# 7SegClock.net
KiCad netlist of a schematic drawn in EAGLE
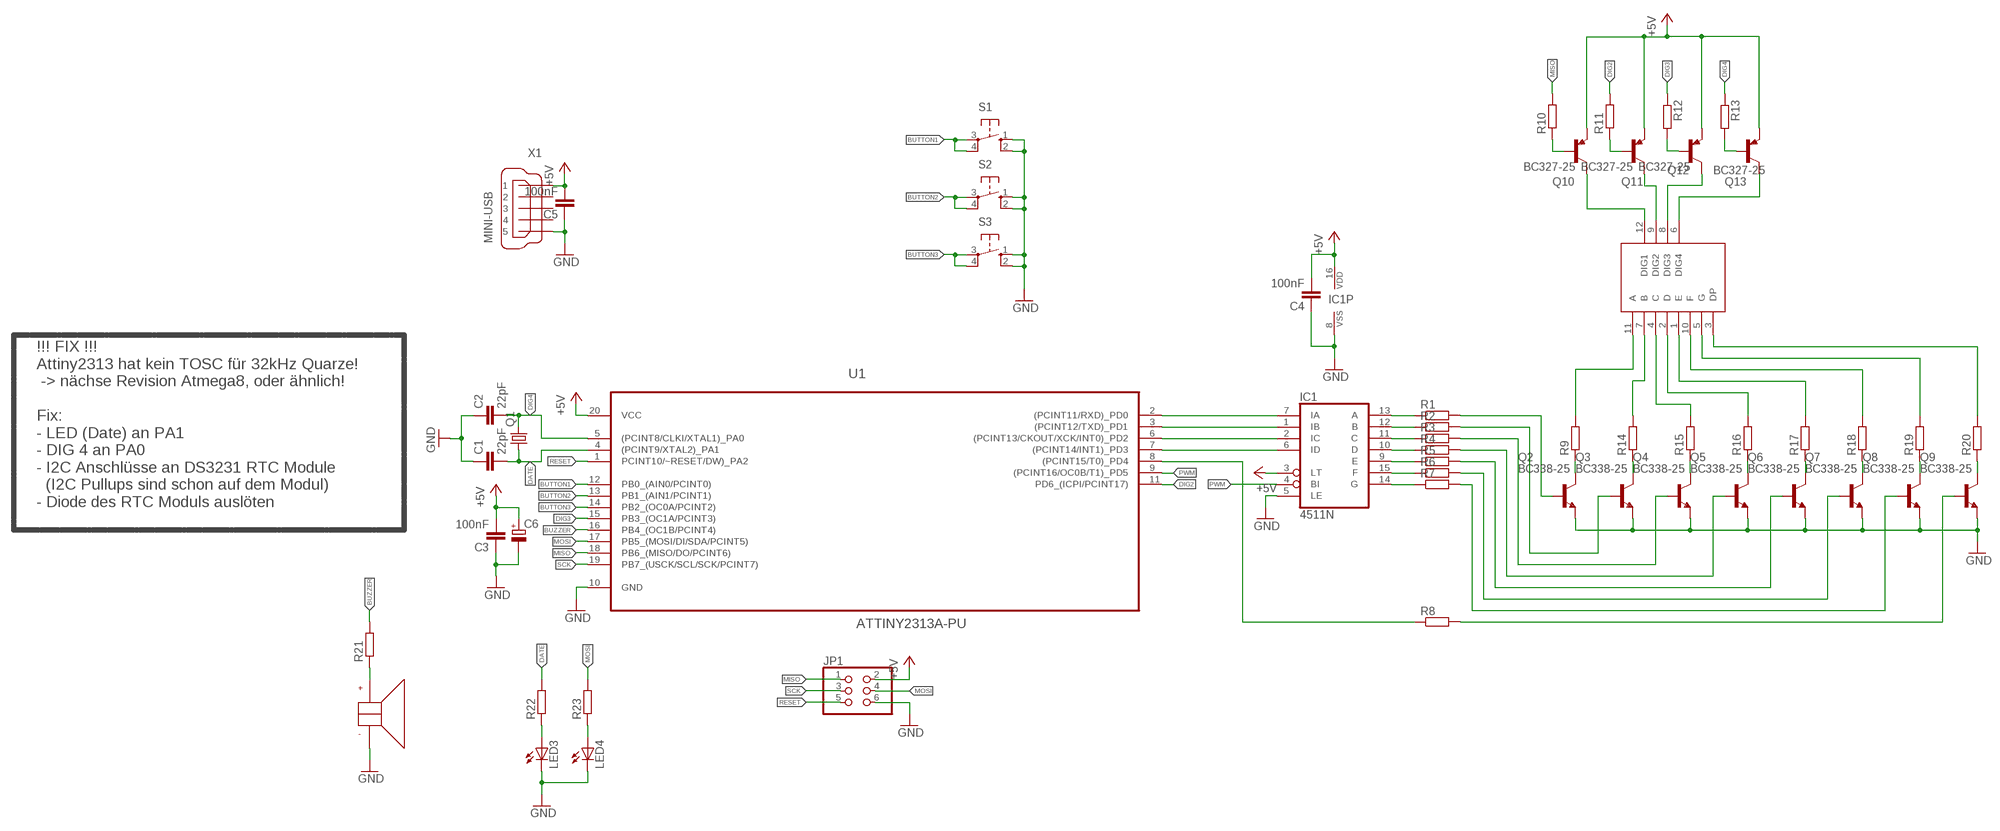
[diagram p0: schematic, sheet 1]

(export (version "E")
  (design (tool "Eeschema 10.0.6"))
  (components
    (comp (ref "C1")
      (value "22pF")
      (footprint "eagle-import:C025-025X050")
      (libsource (lib "eagle-import") (part "C-EU025-025X050"))
    )
    (comp (ref "C2")
      (value "22pF")
      (footprint "eagle-import:C025-025X050")
      (libsource (lib "eagle-import") (part "C-EU025-025X050"))
    )
    (comp (ref "C3")
      (value "100nF")
      (footprint "eagle-import:C025-025X050")
      (libsource (lib "eagle-import") (part "C-EU025-025X050"))
    )
    (comp (ref "C4")
      (value "100nF")
      (footprint "eagle-import:C025-025X050")
      (libsource (lib "eagle-import") (part "C-EU025-025X050"))
    )
    (comp (ref "C5")
      (value "100nF")
      (footprint "eagle-import:C025-025X050")
      (libsource (lib "eagle-import") (part "C-EU025-025X050"))
    )
    (comp (ref "C6")
      (value "CPOL-EUE2-5")
      (footprint "eagle-import:E2-5")
      (libsource (lib "eagle-import") (part "CPOL-EUE2-5"))
    )
    (comp (ref "IC1")
      (value "4511N")
      (footprint "eagle-import:DIL16")
      (libsource (lib "eagle-import") (part "4511N"))
    )
    (comp (ref "JP1")
      (value "PINHD-2X3")
      (footprint "eagle-import:2X03")
      (libsource (lib "eagle-import") (part "PINHD-2X3"))
    )
    (comp (ref "LED1")
      (value "7SEGCOMAN")
      (footprint "eagle-import:7SEGCOMAN")
      (libsource (lib "eagle-import") (part "7SEGCOMAN"))
    )
    (comp (ref "LED3")
      (value "LED3MM")
      (footprint "eagle-import:LED3MM")
      (libsource (lib "eagle-import") (part "LED3MM"))
    )
    (comp (ref "LED4")
      (value "LED3MM")
      (footprint "eagle-import:LED3MM")
      (libsource (lib "eagle-import") (part "LED3MM"))
    )
    (comp (ref "Q1")
      (value "CRYSTALTC38H")
      (footprint "eagle-import:TC38H")
      (libsource (lib "eagle-import") (part "CRYSTALTC38H"))
    )
    (comp (ref "Q2")
      (value "BC338-25")
      (footprint "eagle-import:TO92-EBC")
      (libsource (lib "eagle-import") (part "BC338-25"))
    )
    (comp (ref "Q3")
      (value "BC338-25")
      (footprint "eagle-import:TO92-EBC")
      (libsource (lib "eagle-import") (part "BC338-25"))
    )
    (comp (ref "Q4")
      (value "BC338-25")
      (footprint "eagle-import:TO92-EBC")
      (libsource (lib "eagle-import") (part "BC338-25"))
    )
    (comp (ref "Q5")
      (value "BC338-25")
      (footprint "eagle-import:TO92-EBC")
      (libsource (lib "eagle-import") (part "BC338-25"))
    )
    (comp (ref "Q6")
      (value "BC338-25")
      (footprint "eagle-import:TO92-EBC")
      (libsource (lib "eagle-import") (part "BC338-25"))
    )
    (comp (ref "Q7")
      (value "BC338-25")
      (footprint "eagle-import:TO92-EBC")
      (libsource (lib "eagle-import") (part "BC338-25"))
    )
    (comp (ref "Q8")
      (value "BC338-25")
      (footprint "eagle-import:TO92-EBC")
      (libsource (lib "eagle-import") (part "BC338-25"))
    )
    (comp (ref "Q9")
      (value "BC338-25")
      (footprint "eagle-import:TO92-EBC")
      (libsource (lib "eagle-import") (part "BC338-25"))
    )
    (comp (ref "Q10")
      (value "BC327-25")
      (footprint "eagle-import:TO92-EBC")
      (libsource (lib "eagle-import") (part "BC327-25"))
    )
    (comp (ref "Q11")
      (value "BC327-25")
      (footprint "eagle-import:TO92-EBC")
      (libsource (lib "eagle-import") (part "BC327-25"))
    )
    (comp (ref "Q12")
      (value "BC327-25")
      (footprint "eagle-import:TO92-EBC")
      (libsource (lib "eagle-import") (part "BC327-25"))
    )
    (comp (ref "Q13")
      (value "BC327-25")
      (footprint "eagle-import:TO92-EBC")
      (libsource (lib "eagle-import") (part "BC327-25"))
    )
    (comp (ref "R1")
      (value "R-EU_0207/7")
      (footprint "eagle-import:0207_7")
      (libsource (lib "eagle-import") (part "R-EU_0207/7"))
    )
    (comp (ref "R2")
      (value "R-EU_0207/7")
      (footprint "eagle-import:0207_7")
      (libsource (lib "eagle-import") (part "R-EU_0207/7"))
    )
    (comp (ref "R3")
      (value "R-EU_0207/7")
      (footprint "eagle-import:0207_7")
      (libsource (lib "eagle-import") (part "R-EU_0207/7"))
    )
    (comp (ref "R4")
      (value "R-EU_0207/7")
      (footprint "eagle-import:0207_7")
      (libsource (lib "eagle-import") (part "R-EU_0207/7"))
    )
    (comp (ref "R5")
      (value "R-EU_0207/7")
      (footprint "eagle-import:0207_7")
      (libsource (lib "eagle-import") (part "R-EU_0207/7"))
    )
    (comp (ref "R6")
      (value "R-EU_0207/7")
      (footprint "eagle-import:0207_7")
      (libsource (lib "eagle-import") (part "R-EU_0207/7"))
    )
    (comp (ref "R7")
      (value "R-EU_0207/7")
      (footprint "eagle-import:0207_7")
      (libsource (lib "eagle-import") (part "R-EU_0207/7"))
    )
    (comp (ref "R8")
      (value "R-EU_0207/7")
      (footprint "eagle-import:0207_7")
      (libsource (lib "eagle-import") (part "R-EU_0207/7"))
    )
    (comp (ref "R9")
      (value "R-EU_0207/7")
      (footprint "eagle-import:0207_7")
      (libsource (lib "eagle-import") (part "R-EU_0207/7"))
    )
    (comp (ref "R10")
      (value "R-EU_0207/7")
      (footprint "eagle-import:0207_7")
      (libsource (lib "eagle-import") (part "R-EU_0207/7"))
    )
    (comp (ref "R11")
      (value "R-EU_0207/7")
      (footprint "eagle-import:0207_7")
      (libsource (lib "eagle-import") (part "R-EU_0207/7"))
    )
    (comp (ref "R12")
      (value "R-EU_0207/7")
      (footprint "eagle-import:0207_7")
      (libsource (lib "eagle-import") (part "R-EU_0207/7"))
    )
    (comp (ref "R13")
      (value "R-EU_0207/7")
      (footprint "eagle-import:0207_7")
      (libsource (lib "eagle-import") (part "R-EU_0207/7"))
    )
    (comp (ref "R14")
      (value "R-EU_0207/7")
      (footprint "eagle-import:0207_7")
      (libsource (lib "eagle-import") (part "R-EU_0207/7"))
    )
    (comp (ref "R15")
      (value "R-EU_0207/7")
      (footprint "eagle-import:0207_7")
      (libsource (lib "eagle-import") (part "R-EU_0207/7"))
    )
    (comp (ref "R16")
      (value "R-EU_0207/7")
      (footprint "eagle-import:0207_7")
      (libsource (lib "eagle-import") (part "R-EU_0207/7"))
    )
    (comp (ref "R17")
      (value "R-EU_0207/7")
      (footprint "eagle-import:0207_7")
      (libsource (lib "eagle-import") (part "R-EU_0207/7"))
    )
    (comp (ref "R18")
      (value "R-EU_0207/7")
      (footprint "eagle-import:0207_7")
      (libsource (lib "eagle-import") (part "R-EU_0207/7"))
    )
    (comp (ref "R19")
      (value "R-EU_0207/7")
      (footprint "eagle-import:0207_7")
      (libsource (lib "eagle-import") (part "R-EU_0207/7"))
    )
    (comp (ref "R20")
      (value "R-EU_0207/7")
      (footprint "eagle-import:0207_7")
      (libsource (lib "eagle-import") (part "R-EU_0207/7"))
    )
    (comp (ref "R21")
      (value "R-EU_0207/7")
      (footprint "eagle-import:0207_7")
      (libsource (lib "eagle-import") (part "R-EU_0207/7"))
    )
    (comp (ref "R22")
      (value "R-EU_0207/7")
      (footprint "eagle-import:0207_7")
      (libsource (lib "eagle-import") (part "R-EU_0207/7"))
    )
    (comp (ref "R23")
      (value "R-EU_0207/7")
      (footprint "eagle-import:0207_7")
      (libsource (lib "eagle-import") (part "R-EU_0207/7"))
    )
    (comp (ref "S1")
      (value "10-XX")
      (footprint "eagle-import:B3F-10XX")
      (fields (field (name "MPN") "B3F-1000"))
      (libsource (lib "eagle-import") (part "10-XX"))
    )
    (comp (ref "S2")
      (value "10-XX")
      (footprint "eagle-import:B3F-10XX")
      (fields (field (name "MPN") "B3F-1000"))
      (libsource (lib "eagle-import") (part "10-XX"))
    )
    (comp (ref "S3")
      (value "10-XX")
      (footprint "eagle-import:B3F-10XX")
      (fields (field (name "MPN") "B3F-1000"))
      (libsource (lib "eagle-import") (part "10-XX"))
    )
    (comp (ref "U$1")
      (value "PIEZO_BUZZER_RM7,6")
      (footprint "eagle-import:PIEZO_BUZZER_RM7,6")
      (libsource (lib "eagle-import") (part "PIEZO_BUZZER_RM7,6"))
    )
    (comp (ref "U1")
      (value "ATTINY2313A-PU")
      (footprint "eagle-import:DIP254P762X533-20")
      (libsource (lib "eagle-import") (part "ATTINY2313A-PU"))
    )
    (comp (ref "X1")
      (value "MINI-USB")
      (footprint "eagle-import:32005-201")
      (libsource (lib "eagle-import") (part "MINI-USB-32005-201"))
    )
  )
  (nets
    (net (code "1") (name "+5V") (class "Default")
      (node (ref "C3") (pin "2") (pinfunction "2_2") (pintype "passive"))
      (node (ref "C4") (pin "2") (pinfunction "2_2") (pintype "passive"))
      (node (ref "C5") (pin "2") (pinfunction "2_2") (pintype "passive"))
      (node (ref "C6") (pin "+") (pinfunction "+_+") (pintype "passive"))
      (node (ref "IC1") (pin "16") (pinfunction "VDD_16") (pintype "power_in"))
      (node (ref "IC1") (pin "3") (pinfunction "LT_3") (pintype "input"))
      (node (ref "JP1") (pin "2") (pinfunction "2_2") (pintype "passive"))
      (node (ref "Q10") (pin "E") (pinfunction "E_E") (pintype "passive"))
      (node (ref "Q11") (pin "E") (pinfunction "E_E") (pintype "passive"))
      (node (ref "Q12") (pin "E") (pinfunction "E_E") (pintype "passive"))
      (node (ref "Q13") (pin "E") (pinfunction "E_E") (pintype "passive"))
      (node (ref "U1") (pin "20") (pinfunction "VCC_20") (pintype "power_in"))
      (node (ref "X1") (pin "1") (pinfunction "1_1") (pintype "passive"))
    )
    (net (code "2") (name "BUTTON1") (class "Default")
      (node (ref "S1") (pin "3") (pinfunction "P_3") (pintype "passive"))
      (node (ref "S1") (pin "4") (pinfunction "P1_4") (pintype "passive"))
      (node (ref "U1") (pin "12") (pinfunction "PB0_(AIN0/PCINT0)_12") (pintype "bidirectional"))
    )
    (net (code "3") (name "BUTTON2") (class "Default")
      (node (ref "S2") (pin "3") (pinfunction "P_3") (pintype "passive"))
      (node (ref "S2") (pin "4") (pinfunction "P1_4") (pintype "passive"))
      (node (ref "U1") (pin "13") (pinfunction "PB1_(AIN1/PCINT1)_13") (pintype "bidirectional"))
    )
    (net (code "4") (name "BUTTON3") (class "Default")
      (node (ref "S3") (pin "3") (pinfunction "P_3") (pintype "passive"))
      (node (ref "S3") (pin "4") (pinfunction "P1_4") (pintype "passive"))
      (node (ref "U1") (pin "14") (pinfunction "PB2_(OC0A/PCINT2)_14") (pintype "bidirectional"))
    )
    (net (code "5") (name "BUZZER") (class "Default")
      (node (ref "R21") (pin "2") (pinfunction "2_2") (pintype "passive"))
      (node (ref "U1") (pin "16") (pinfunction "PB4_(OC1B/PCINT4)_16") (pintype "bidirectional"))
    )
    (net (code "6") (name "DATE") (class "Default")
      (node (ref "C1") (pin "2") (pinfunction "2_2") (pintype "passive"))
      (node (ref "Q1") (pin "1") (pinfunction "1_1") (pintype "passive"))
      (node (ref "R22") (pin "2") (pinfunction "2_2") (pintype "passive"))
      (node (ref "U1") (pin "4") (pinfunction "(PCINT9/XTAL2)_PA1_4") (pintype "bidirectional"))
    )
    (net (code "7") (name "DIG2") (class "Default")
      (node (ref "R11") (pin "2") (pinfunction "2_2") (pintype "passive"))
      (node (ref "U1") (pin "11") (pinfunction "PD6_(ICPI/PCINT17)_11") (pintype "bidirectional"))
    )
    (net (code "8") (name "DIG3") (class "Default")
      (node (ref "R12") (pin "1") (pinfunction "1_1") (pintype "passive"))
      (node (ref "U1") (pin "15") (pinfunction "PB3_(OC1A/PCINT3)_15") (pintype "bidirectional"))
    )
    (net (code "9") (name "DIG4") (class "Default")
      (node (ref "C2") (pin "2") (pinfunction "2_2") (pintype "passive"))
      (node (ref "Q1") (pin "2") (pinfunction "2_2") (pintype "passive"))
      (node (ref "R13") (pin "1") (pinfunction "1_1") (pintype "passive"))
      (node (ref "U1") (pin "5") (pinfunction "(PCINT8/CLKI/XTAL1)_PA0_5") (pintype "bidirectional"))
    )
    (net (code "10") (name "GND") (class "Default")
      (node (ref "C1") (pin "1") (pinfunction "1_1") (pintype "passive"))
      (node (ref "C2") (pin "1") (pinfunction "1_1") (pintype "passive"))
      (node (ref "C3") (pin "1") (pinfunction "1_1") (pintype "passive"))
      (node (ref "C4") (pin "1") (pinfunction "1_1") (pintype "passive"))
      (node (ref "C5") (pin "1") (pinfunction "1_1") (pintype "passive"))
      (node (ref "C6") (pin "-") (pinfunction "-_-") (pintype "passive"))
      (node (ref "IC1") (pin "5") (pinfunction "LE_5") (pintype "input"))
      (node (ref "IC1") (pin "8") (pinfunction "VSS_8") (pintype "power_in"))
      (node (ref "JP1") (pin "6") (pinfunction "6_6") (pintype "passive"))
      (node (ref "LED3") (pin "K") (pinfunction "C_K") (pintype "passive"))
      (node (ref "LED4") (pin "K") (pinfunction "C_K") (pintype "passive"))
      (node (ref "Q2") (pin "E") (pinfunction "E_E") (pintype "passive"))
      (node (ref "Q3") (pin "E") (pinfunction "E_E") (pintype "passive"))
      (node (ref "Q4") (pin "E") (pinfunction "E_E") (pintype "passive"))
      (node (ref "Q5") (pin "E") (pinfunction "E_E") (pintype "passive"))
      (node (ref "Q6") (pin "E") (pinfunction "E_E") (pintype "passive"))
      (node (ref "Q7") (pin "E") (pinfunction "E_E") (pintype "passive"))
      (node (ref "Q8") (pin "E") (pinfunction "E_E") (pintype "passive"))
      (node (ref "Q9") (pin "E") (pinfunction "E_E") (pintype "passive"))
      (node (ref "S1") (pin "1") (pinfunction "S_1") (pintype "passive"))
      (node (ref "S1") (pin "2") (pinfunction "S1_2") (pintype "passive"))
      (node (ref "S2") (pin "1") (pinfunction "S_1") (pintype "passive"))
      (node (ref "S2") (pin "2") (pinfunction "S1_2") (pintype "passive"))
      (node (ref "S3") (pin "1") (pinfunction "S_1") (pintype "passive"))
      (node (ref "S3") (pin "2") (pinfunction "S1_2") (pintype "passive"))
      (node (ref "U$1") (pin "P$2") (pinfunction "P$2_P$2") (pintype "bidirectional"))
      (node (ref "U1") (pin "10") (pinfunction "GND_10") (pintype "passive"))
      (node (ref "X1") (pin "5") (pinfunction "5_5") (pintype "passive"))
    )
    (net (code "11") (name "MISO") (class "Default")
      (node (ref "JP1") (pin "1") (pinfunction "1_1") (pintype "passive"))
      (node (ref "R10") (pin "2") (pinfunction "2_2") (pintype "passive"))
      (node (ref "U1") (pin "18") (pinfunction "PB6_(MISO/DO/PCINT6)_18") (pintype "bidirectional"))
    )
    (net (code "12") (name "MOSI") (class "Default")
      (node (ref "JP1") (pin "4") (pinfunction "4_4") (pintype "passive"))
      (node (ref "R23") (pin "2") (pinfunction "2_2") (pintype "passive"))
      (node (ref "U1") (pin "17") (pinfunction "PB5_(MOSI/DI/SDA/PCINT5)_17") (pintype "bidirectional"))
    )
    (net (code "13") (name "Net-(IC1A-A)") (class "Default")
      (node (ref "IC1") (pin "13") (pinfunction "A_13") (pintype "output"))
      (node (ref "R1") (pin "1") (pinfunction "1_1") (pintype "passive"))
    )
    (net (code "14") (name "Net-(IC1A-B)") (class "Default")
      (node (ref "IC1") (pin "12") (pinfunction "B_12") (pintype "output"))
      (node (ref "R2") (pin "1") (pinfunction "1_1") (pintype "passive"))
    )
    (net (code "15") (name "Net-(IC1A-C)") (class "Default")
      (node (ref "IC1") (pin "11") (pinfunction "C_11") (pintype "output"))
      (node (ref "R3") (pin "1") (pinfunction "1_1") (pintype "passive"))
    )
    (net (code "16") (name "Net-(IC1A-D)") (class "Default")
      (node (ref "IC1") (pin "10") (pinfunction "D_10") (pintype "output"))
      (node (ref "R4") (pin "1") (pinfunction "1_1") (pintype "passive"))
    )
    (net (code "17") (name "Net-(IC1A-E)") (class "Default")
      (node (ref "IC1") (pin "9") (pinfunction "E_9") (pintype "output"))
      (node (ref "R5") (pin "1") (pinfunction "1_1") (pintype "passive"))
    )
    (net (code "18") (name "Net-(IC1A-F)") (class "Default")
      (node (ref "IC1") (pin "15") (pinfunction "F_15") (pintype "output"))
      (node (ref "R6") (pin "1") (pinfunction "1_1") (pintype "passive"))
    )
    (net (code "19") (name "Net-(IC1A-G)") (class "Default")
      (node (ref "IC1") (pin "14") (pinfunction "G_14") (pintype "output"))
      (node (ref "R7") (pin "1") (pinfunction "1_1") (pintype "passive"))
    )
    (net (code "20") (name "Net-(IC1A-IA)") (class "Default")
      (node (ref "IC1") (pin "7") (pinfunction "IA_7") (pintype "input"))
      (node (ref "U1") (pin "2") (pinfunction "(PCINT11/RXD)_PD0_2") (pintype "bidirectional"))
    )
    (net (code "21") (name "Net-(IC1A-IB)") (class "Default")
      (node (ref "IC1") (pin "1") (pinfunction "IB_1") (pintype "input"))
      (node (ref "U1") (pin "3") (pinfunction "(PCINT12/TXD)_PD1_3") (pintype "bidirectional"))
    )
    (net (code "22") (name "Net-(IC1A-IC)") (class "Default")
      (node (ref "IC1") (pin "2") (pinfunction "IC_2") (pintype "input"))
      (node (ref "U1") (pin "6") (pinfunction "(PCINT13/CKOUT/XCK/INT0)_PD2_6") (pintype "bidirectional"))
    )
    (net (code "23") (name "Net-(IC1A-ID)") (class "Default")
      (node (ref "IC1") (pin "6") (pinfunction "ID_6") (pintype "input"))
      (node (ref "U1") (pin "7") (pinfunction "(PCINT14/INT1)_PD3_7") (pintype "bidirectional"))
    )
    (net (code "24") (name "Net-(LED1-A)") (class "Default")
      (node (ref "LED1") (pin "11") (pinfunction "A_11") (pintype "bidirectional"))
      (node (ref "R9") (pin "2") (pinfunction "2_2") (pintype "passive"))
    )
    (net (code "25") (name "Net-(LED1-B)") (class "Default")
      (node (ref "LED1") (pin "7") (pinfunction "B_7") (pintype "bidirectional"))
      (node (ref "R14") (pin "2") (pinfunction "2_2") (pintype "passive"))
    )
    (net (code "26") (name "Net-(LED1-C)") (class "Default")
      (node (ref "LED1") (pin "4") (pinfunction "C_4") (pintype "bidirectional"))
      (node (ref "R15") (pin "2") (pinfunction "2_2") (pintype "passive"))
    )
    (net (code "27") (name "Net-(LED1-D)") (class "Default")
      (node (ref "LED1") (pin "2") (pinfunction "D_2") (pintype "bidirectional"))
      (node (ref "R16") (pin "2") (pinfunction "2_2") (pintype "passive"))
    )
    (net (code "28") (name "Net-(LED1-DIG1)") (class "Default")
      (node (ref "LED1") (pin "12") (pinfunction "DIG1_12") (pintype "bidirectional"))
      (node (ref "Q10") (pin "C") (pinfunction "C_C") (pintype "passive"))
    )
    (net (code "29") (name "Net-(LED1-DIG2)") (class "Default")
      (node (ref "LED1") (pin "9") (pinfunction "DIG2_9") (pintype "bidirectional"))
      (node (ref "Q11") (pin "C") (pinfunction "C_C") (pintype "passive"))
    )
    (net (code "30") (name "Net-(LED1-DIG3)") (class "Default")
      (node (ref "LED1") (pin "8") (pinfunction "DIG3_8") (pintype "bidirectional"))
      (node (ref "Q12") (pin "C") (pinfunction "C_C") (pintype "passive"))
    )
    (net (code "31") (name "Net-(LED1-DIG4)") (class "Default")
      (node (ref "LED1") (pin "6") (pinfunction "DIG4_6") (pintype "bidirectional"))
      (node (ref "Q13") (pin "C") (pinfunction "C_C") (pintype "passive"))
    )
    (net (code "32") (name "Net-(LED1-DP)") (class "Default")
      (node (ref "LED1") (pin "3") (pinfunction "DP_3") (pintype "bidirectional"))
      (node (ref "R20") (pin "2") (pinfunction "2_2") (pintype "passive"))
    )
    (net (code "33") (name "Net-(LED1-E)") (class "Default")
      (node (ref "LED1") (pin "1") (pinfunction "E_1") (pintype "bidirectional"))
      (node (ref "R17") (pin "2") (pinfunction "2_2") (pintype "passive"))
    )
    (net (code "34") (name "Net-(LED1-F)") (class "Default")
      (node (ref "LED1") (pin "10") (pinfunction "F_10") (pintype "bidirectional"))
      (node (ref "R18") (pin "2") (pinfunction "2_2") (pintype "passive"))
    )
    (net (code "35") (name "Net-(LED1-G)") (class "Default")
      (node (ref "LED1") (pin "5") (pinfunction "G_5") (pintype "bidirectional"))
      (node (ref "R19") (pin "2") (pinfunction "2_2") (pintype "passive"))
    )
    (net (code "36") (name "Net-(LED3-PadA)") (class "Default")
      (node (ref "LED3") (pin "A") (pinfunction "A_A") (pintype "passive"))
      (node (ref "R22") (pin "1") (pinfunction "1_1") (pintype "passive"))
    )
    (net (code "37") (name "Net-(LED4-PadA)") (class "Default")
      (node (ref "LED4") (pin "A") (pinfunction "A_A") (pintype "passive"))
      (node (ref "R23") (pin "1") (pinfunction "1_1") (pintype "passive"))
    )
    (net (code "38") (name "Net-(Q2-PadB)") (class "Default")
      (node (ref "Q2") (pin "B") (pinfunction "B_B") (pintype "passive"))
      (node (ref "R1") (pin "2") (pinfunction "2_2") (pintype "passive"))
    )
    (net (code "39") (name "Net-(Q2-PadC)") (class "Default")
      (node (ref "Q2") (pin "C") (pinfunction "C_C") (pintype "passive"))
      (node (ref "R9") (pin "1") (pinfunction "1_1") (pintype "passive"))
    )
    (net (code "40") (name "Net-(Q3-PadB)") (class "Default")
      (node (ref "Q3") (pin "B") (pinfunction "B_B") (pintype "passive"))
      (node (ref "R2") (pin "2") (pinfunction "2_2") (pintype "passive"))
    )
    (net (code "41") (name "Net-(Q3-PadC)") (class "Default")
      (node (ref "Q3") (pin "C") (pinfunction "C_C") (pintype "passive"))
      (node (ref "R14") (pin "1") (pinfunction "1_1") (pintype "passive"))
    )
    (net (code "42") (name "Net-(Q4-PadB)") (class "Default")
      (node (ref "Q4") (pin "B") (pinfunction "B_B") (pintype "passive"))
      (node (ref "R3") (pin "2") (pinfunction "2_2") (pintype "passive"))
    )
    (net (code "43") (name "Net-(Q4-PadC)") (class "Default")
      (node (ref "Q4") (pin "C") (pinfunction "C_C") (pintype "passive"))
      (node (ref "R15") (pin "1") (pinfunction "1_1") (pintype "passive"))
    )
    (net (code "44") (name "Net-(Q5-PadB)") (class "Default")
      (node (ref "Q5") (pin "B") (pinfunction "B_B") (pintype "passive"))
      (node (ref "R4") (pin "2") (pinfunction "2_2") (pintype "passive"))
    )
    (net (code "45") (name "Net-(Q5-PadC)") (class "Default")
      (node (ref "Q5") (pin "C") (pinfunction "C_C") (pintype "passive"))
      (node (ref "R16") (pin "1") (pinfunction "1_1") (pintype "passive"))
    )
    (net (code "46") (name "Net-(Q6-PadB)") (class "Default")
      (node (ref "Q6") (pin "B") (pinfunction "B_B") (pintype "passive"))
      (node (ref "R5") (pin "2") (pinfunction "2_2") (pintype "passive"))
    )
    (net (code "47") (name "Net-(Q6-PadC)") (class "Default")
      (node (ref "Q6") (pin "C") (pinfunction "C_C") (pintype "passive"))
      (node (ref "R17") (pin "1") (pinfunction "1_1") (pintype "passive"))
    )
    (net (code "48") (name "Net-(Q7-PadB)") (class "Default")
      (node (ref "Q7") (pin "B") (pinfunction "B_B") (pintype "passive"))
      (node (ref "R6") (pin "2") (pinfunction "2_2") (pintype "passive"))
    )
    (net (code "49") (name "Net-(Q7-PadC)") (class "Default")
      (node (ref "Q7") (pin "C") (pinfunction "C_C") (pintype "passive"))
      (node (ref "R18") (pin "1") (pinfunction "1_1") (pintype "passive"))
    )
    (net (code "50") (name "Net-(Q8-PadB)") (class "Default")
      (node (ref "Q8") (pin "B") (pinfunction "B_B") (pintype "passive"))
      (node (ref "R7") (pin "2") (pinfunction "2_2") (pintype "passive"))
    )
    (net (code "51") (name "Net-(Q8-PadC)") (class "Default")
      (node (ref "Q8") (pin "C") (pinfunction "C_C") (pintype "passive"))
      (node (ref "R19") (pin "1") (pinfunction "1_1") (pintype "passive"))
    )
    (net (code "52") (name "Net-(Q9-PadB)") (class "Default")
      (node (ref "Q9") (pin "B") (pinfunction "B_B") (pintype "passive"))
      (node (ref "R8") (pin "2") (pinfunction "2_2") (pintype "passive"))
    )
    (net (code "53") (name "Net-(Q9-PadC)") (class "Default")
      (node (ref "Q9") (pin "C") (pinfunction "C_C") (pintype "passive"))
      (node (ref "R20") (pin "1") (pinfunction "1_1") (pintype "passive"))
    )
    (net (code "54") (name "Net-(Q10-PadB)") (class "Default")
      (node (ref "Q10") (pin "B") (pinfunction "B_B") (pintype "passive"))
      (node (ref "R10") (pin "1") (pinfunction "1_1") (pintype "passive"))
    )
    (net (code "55") (name "Net-(Q11-PadB)") (class "Default")
      (node (ref "Q11") (pin "B") (pinfunction "B_B") (pintype "passive"))
      (node (ref "R11") (pin "1") (pinfunction "1_1") (pintype "passive"))
    )
    (net (code "56") (name "Net-(Q12-PadB)") (class "Default")
      (node (ref "Q12") (pin "B") (pinfunction "B_B") (pintype "passive"))
      (node (ref "R12") (pin "2") (pinfunction "2_2") (pintype "passive"))
    )
    (net (code "57") (name "Net-(Q13-PadB)") (class "Default")
      (node (ref "Q13") (pin "B") (pinfunction "B_B") (pintype "passive"))
      (node (ref "R13") (pin "2") (pinfunction "2_2") (pintype "passive"))
    )
    (net (code "58") (name "Net-(R21-Pad1)") (class "Default")
      (node (ref "R21") (pin "1") (pinfunction "1_1") (pintype "passive"))
      (node (ref "U$1") (pin "P$1") (pinfunction "P$1_P$1") (pintype "bidirectional"))
    )
    (net (code "59") (name "Net-(U1-(PCINT15{slash}T0)_PD4)") (class "Default")
      (node (ref "R8") (pin "1") (pinfunction "1_1") (pintype "passive"))
      (node (ref "U1") (pin "8") (pinfunction "(PCINT15/T0)_PD4_8") (pintype "bidirectional"))
    )
    (net (code "60") (name "PWM") (class "Default")
      (node (ref "IC1") (pin "4") (pinfunction "BI_4") (pintype "input"))
      (node (ref "U1") (pin "9") (pinfunction "(PCINT16/OC0B/T1)_PD5_9") (pintype "bidirectional"))
    )
    (net (code "61") (name "RESET") (class "Default")
      (node (ref "JP1") (pin "5") (pinfunction "5_5") (pintype "passive"))
      (node (ref "U1") (pin "1") (pinfunction "PCINT10/~{RESET/DW})_PA2_1") (pintype "bidirectional"))
    )
    (net (code "62") (name "SCK") (class "Default")
      (node (ref "JP1") (pin "3") (pinfunction "3_3") (pintype "passive"))
      (node (ref "U1") (pin "19") (pinfunction "PB7_(USCK/SCL/SCK/PCINT7)_19") (pintype "bidirectional"))
    )
    (net (code "63") (name "unconnected-(X1-Pad2)") (class "Default")
      (node (ref "X1") (pin "2") (pinfunction "2_2") (pintype "passive"))
    )
    (net (code "64") (name "unconnected-(X1-Pad3)") (class "Default")
      (node (ref "X1") (pin "3") (pinfunction "3_3") (pintype "passive"))
    )
    (net (code "65") (name "unconnected-(X1-Pad4)") (class "Default")
      (node (ref "X1") (pin "4") (pinfunction "4_4") (pintype "passive"))
    )
  )
)
